# connectors.net
KiCad netlist of a schematic drawn in Altium Designer
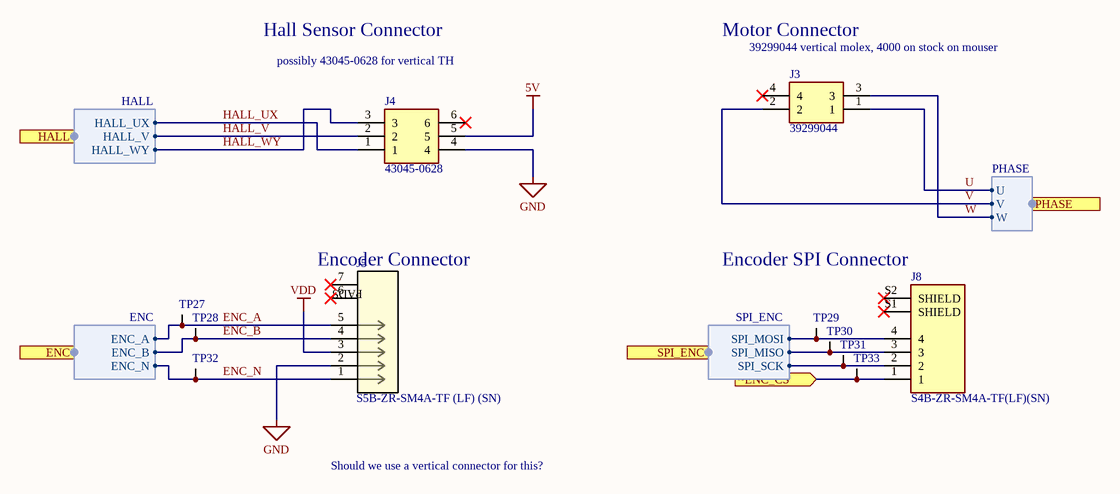
[diagram p0: connectors.SchDoc]

(export (version "E")
  (design (tool "Eeschema 10.0.6"))
  (components
    (comp (ref "J3")
      (value "39299044")
      (footprint "39299044")
      (description "Molex 39299044 4POS Minifit\r\ndual row, vertical")
      (fields (field (name "PART NUMBER") "CN HDR 4POS Molex 39299044 VERT"))
      (libsource (lib "Connector_Library") (part "CN HDR 4POS Molex 39299044 VERT"))
    )
    (comp (ref "J4")
      (value "43045-0628")
      (footprint "430450628")
      (description "Molex 43045-0628 6POS Microfit\r\ndual row, Vertical")
      (fields (field (name "PART NUMBER") "CN HDR 6POS Molex 43045-0628"))
      (libsource (lib "Connector_Library") (part "CN HDR 6POS Molex 43045-0628"))
    )
    (comp (ref "J5")
      (value "S5B-ZR-SM4A-TF (LF) (SN)")
      (footprint "JST_S5B-ZR-SM4A-TF")
      (description "Connector Header Surface Mount, Right Angle 5 position 0.059\" (1.50mm)")
      (fields (field (name "PART NUMBER") "CN 5POS JST ZR RA"))
      (libsource (lib "Connector_Library") (part "CN 5POS JST ZR RA"))
    )
    (comp (ref "J8")
      (value "S4B-ZR-SM4A-TF(LF)(SN)")
      (footprint "JST_S4B-ZR-SM4A-TF(LF)(SN)")
      (description "Connector Header Surface Mount, Right Angle 4 position 0.059 (1.50mm)")
      (fields (field (name "MF") "JST Sales") (field (name "PART NUMBER") "CN 4POS JST ZR RA"))
      (libsource (lib "Connector_Library") (part "CN HDR 4POS SMD JST ZR"))
    )
    (comp (ref "TP27")
      (value "ENC_A")
      (footprint "TP")
      (fields (field (name "PART NUMBER") "Test Point (Via)"))
      (libsource (lib "IC_Library") (part "Test Point (Via)"))
    )
    (comp (ref "TP28")
      (value "ENC_B")
      (footprint "TP")
      (fields (field (name "PART NUMBER") "Test Point (Via)"))
      (libsource (lib "IC_Library") (part "Test Point (Via)"))
    )
    (comp (ref "TP29")
      (value "MOSI")
      (footprint "TP")
      (fields (field (name "PART NUMBER") "Test Point (Via)"))
      (libsource (lib "IC_Library") (part "Test Point (Via)"))
    )
    (comp (ref "TP30")
      (value "MISO")
      (footprint "TP")
      (fields (field (name "PART NUMBER") "Test Point (Via)"))
      (libsource (lib "IC_Library") (part "Test Point (Via)"))
    )
    (comp (ref "TP31")
      (value "SCK")
      (footprint "TP")
      (fields (field (name "PART NUMBER") "Test Point (Via)"))
      (libsource (lib "IC_Library") (part "Test Point (Via)"))
    )
    (comp (ref "TP32")
      (value "ENC_N")
      (footprint "TP")
      (fields (field (name "PART NUMBER") "Test Point (Via)"))
      (libsource (lib "IC_Library") (part "Test Point (Via)"))
    )
    (comp (ref "TP33")
      (value "ENC_CS")
      (footprint "TP")
      (fields (field (name "PART NUMBER") "Test Point (Via)"))
      (libsource (lib "IC_Library") (part "Test Point (Via)"))
    )
  )
  (nets
    (net (code "6") (name "/ENC_A") (class "Default")
      (node (ref "J5") (pin "5") (pinfunction "5_5") (pintype "passive"))
      (node (ref "TP27") (pin "1") (pinfunction "1_1") (pintype "passive"))
    )
    (net (code "7") (name "/ENC_B") (class "Default")
      (node (ref "J5") (pin "4") (pinfunction "4_4") (pintype "passive"))
      (node (ref "TP28") (pin "1") (pinfunction "1_1") (pintype "passive"))
    )
    (net (code "8") (name "/ENC_N") (class "Default")
      (node (ref "J5") (pin "1") (pinfunction "1_1") (pintype "passive"))
      (node (ref "TP32") (pin "1") (pinfunction "1_1") (pintype "passive"))
    )
    (net (code "9") (name "/HALL_UX") (class "Default")
      (node (ref "J4") (pin "1") (pinfunction "1_1") (pintype "passive"))
    )
    (net (code "10") (name "/HALL_V") (class "Default")
      (node (ref "J4") (pin "2") (pinfunction "2_2") (pintype "passive"))
    )
    (net (code "11") (name "/HALL_WY") (class "Default")
      (node (ref "J4") (pin "3") (pinfunction "3_3") (pintype "passive"))
    )
    (net (code "13") (name "/U") (class "Default")
      (node (ref "J3") (pin "1") (pinfunction "1_1") (pintype "passive"))
    )
    (net (code "14") (name "/V") (class "Default")
      (node (ref "J3") (pin "2") (pinfunction "2_2") (pintype "passive"))
    )
    (net (code "15") (name "/W") (class "Default")
      (node (ref "J3") (pin "3") (pinfunction "3_3") (pintype "passive"))
    )
    (net (code "19") (name "/{SPI_ENC}") (class "Default")
      (node (ref "J8") (pin "1") (pinfunction "1_1") (pintype "passive"))
      (node (ref "TP33") (pin "1") (pinfunction "1_1") (pintype "passive"))
    )
    (net (code "20") (name "5V") (class "Default")
      (node (ref "J4") (pin "5") (pinfunction "5_5") (pintype "passive"))
    )
    (net (code "21") (name "GND") (class "Default")
      (node (ref "J4") (pin "4") (pinfunction "4_4") (pintype "passive"))
      (node (ref "J5") (pin "2") (pinfunction "2_2") (pintype "passive"))
    )
    (net (code "22") (name "Net-(J8-Pad2)") (class "Default")
      (node (ref "J8") (pin "2") (pinfunction "2_2") (pintype "passive"))
      (node (ref "TP31") (pin "1") (pinfunction "1_1") (pintype "passive"))
    )
    (net (code "23") (name "Net-(J8-Pad3)") (class "Default")
      (node (ref "J8") (pin "3") (pinfunction "3_3") (pintype "passive"))
      (node (ref "TP30") (pin "1") (pinfunction "1_1") (pintype "passive"))
    )
    (net (code "24") (name "Net-(J8-Pad4)") (class "Default")
      (node (ref "J8") (pin "4") (pinfunction "4_4") (pintype "passive"))
      (node (ref "TP29") (pin "1") (pinfunction "1_1") (pintype "passive"))
    )
    (net (code "25") (name "VDD") (class "Default")
      (node (ref "J5") (pin "3") (pinfunction "3_3") (pintype "passive"))
    )
    (net (code "26") (name "unconnected-(J3-Pad4)") (class "Default")
      (node (ref "J3") (pin "4") (pinfunction "4_4") (pintype "passive+no_connect"))
    )
    (net (code "27") (name "unconnected-(J4-Pad6)") (class "Default")
      (node (ref "J4") (pin "6") (pinfunction "6_6") (pintype "passive+no_connect"))
    )
    (net (code "28") (name "unconnected-(J5-Pad6)") (class "Default")
      (node (ref "J5") (pin "6") (pinfunction "6_6") (pintype "passive+no_connect"))
    )
    (net (code "29") (name "unconnected-(J5-Pad7)") (class "Default")
      (node (ref "J5") (pin "7") (pinfunction "7_7") (pintype "passive+no_connect"))
    )
    (net (code "30") (name "unconnected-(J8-SHIELD-PadS1)") (class "Default")
      (node (ref "J8") (pin "S1") (pinfunction "SHIELD_S1") (pintype "passive+no_connect"))
    )
    (net (code "31") (name "unconnected-(J8-SHIELD-PadS2)") (class "Default")
      (node (ref "J8") (pin "S2") (pinfunction "SHIELD_S2") (pintype "passive+no_connect"))
    )
  )
)
